# 3_-_STM32F103_Debugger.net
KiCad netlist of a schematic drawn in Altium Designer
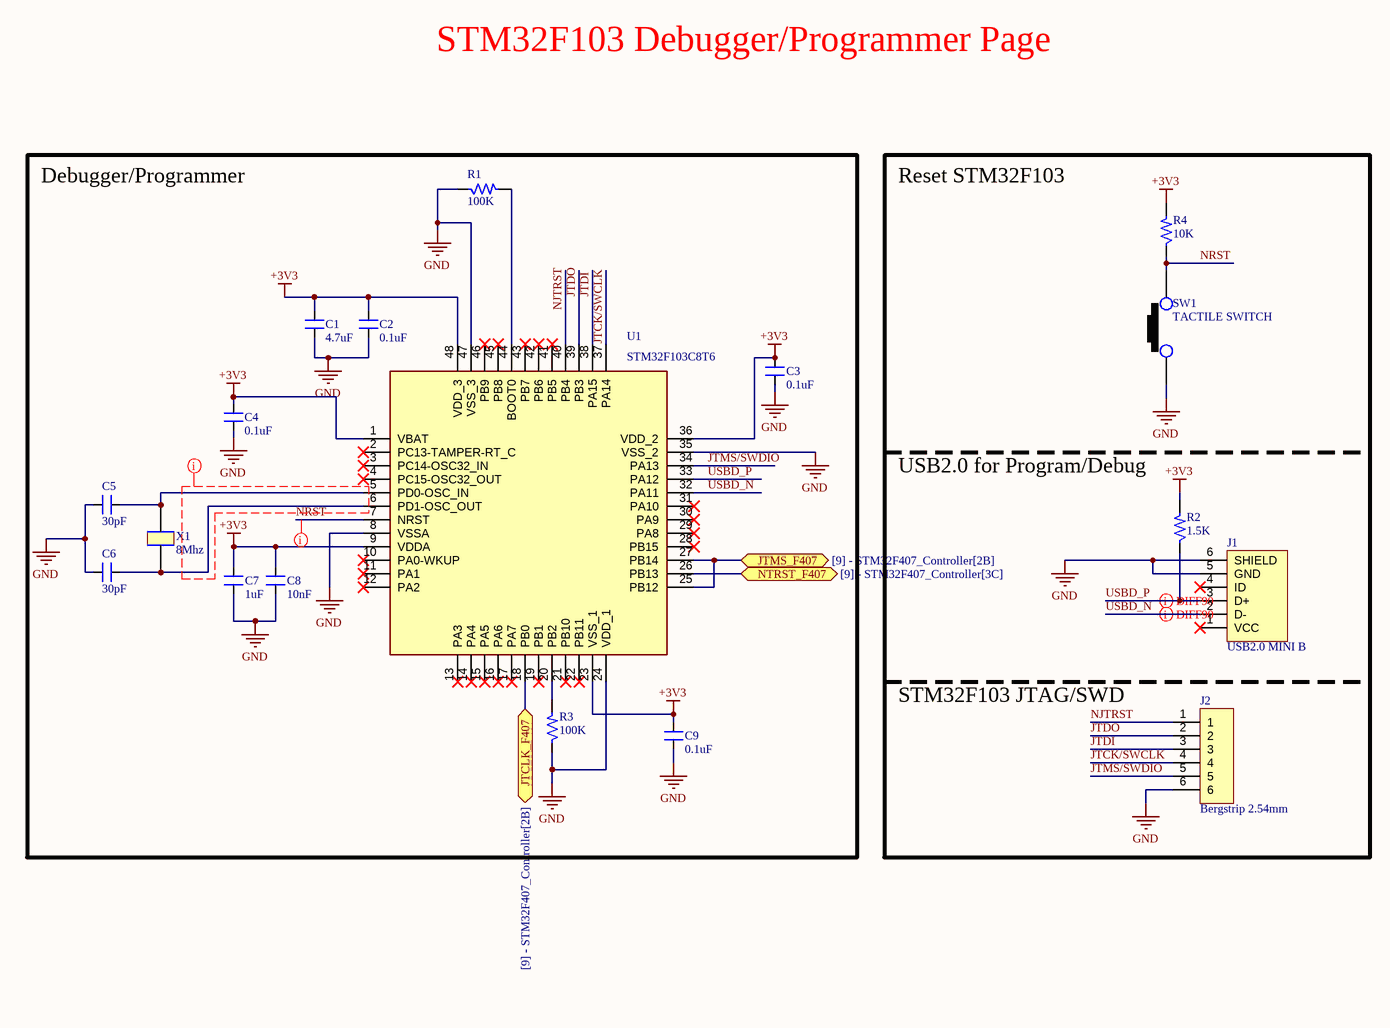
[diagram p0: [3] - STM32F103_Debugger.SchDoc]

(export (version "E")
  (design (tool "Eeschema 10.0.6"))
  (components
    (comp (ref "C1")
      (value "4.7uF")
      (footprint "CAP_0805")
      (description "4.7µF ±10% 50V Ceramic Capacitor X5R 0805 (2012 Metric)")
      (fields
        (field (name "MANUFACTURER") "Yageo")
        (field (name "MANUFACTURER PART NUMBER") "GRM21BR61H475KE51L")
      )
      (libsource (lib "ESTEEMPCBLIB") (part "CAP_4.7uF-50V-10%-0805"))
    )
    (comp (ref "C2")
      (value "0.1uF")
      (footprint "CAP_0805")
      (description "0.1µF ±5% 50V Ceramic Capacitor X7R 0805 (2012 Metric)")
      (fields
        (field (name "MANUFACTURER") "AVX Corporation")
        (field (name "MANUFACTURER PART NUMBER") "08055C104JAT4A")
      )
      (libsource (lib "ESTEEMPCBLIB") (part "CAP_0.1uF-50V-5%-0805"))
    )
    (comp (ref "C3")
      (value "0.1uF")
      (footprint "CAP_0805")
      (description "0.1µF ±5% 50V Ceramic Capacitor X7R 0805 (2012 Metric)")
      (fields
        (field (name "MANUFACTURER") "AVX Corporation")
        (field (name "MANUFACTURER PART NUMBER") "08055C104JAT4A")
      )
      (libsource (lib "ESTEEMPCBLIB") (part "CAP_0.1uF-50V-5%-0805"))
    )
    (comp (ref "C4")
      (value "0.1uF")
      (footprint "CAP_0805")
      (description "0.1µF ±5% 50V Ceramic Capacitor X7R 0805 (2012 Metric)")
      (fields
        (field (name "MANUFACTURER") "AVX Corporation")
        (field (name "MANUFACTURER PART NUMBER") "08055C104JAT4A")
      )
      (libsource (lib "ESTEEMPCBLIB") (part "CAP_0.1uF-50V-5%-0805"))
    )
    (comp (ref "C5")
      (value "30pF")
      (footprint "CAP_0805")
      (description "±10% 50V Ceramic Capacitor C0G, NP0 0805 (2012 Metric)")
      (fields
        (field (name "MANUFACTURER PART NUMBER") "C0805C300K5GAC7800")
        (field (name "MANUFACTURER") "KEMET")
      )
      (libsource (lib "ESTEEMPCBLIB") (part "CAP_30pF-50V-10%-0805"))
    )
    (comp (ref "C6")
      (value "30pF")
      (footprint "CAP_0805")
      (description "±10% 50V Ceramic Capacitor C0G, NP0 0805 (2012 Metric)")
      (fields
        (field (name "MANUFACTURER PART NUMBER") "C0805C300K5GAC7800")
        (field (name "MANUFACTURER") "KEMET")
      )
      (libsource (lib "ESTEEMPCBLIB") (part "CAP_30pF-50V-10%-0805"))
    )
    (comp (ref "C7")
      (value "1uF")
      (footprint "CAP_0805")
      (description "1µF ±5% 50V Ceramic Capacitor X7R 0805 (2012 Metric)")
      (fields
        (field (name "MANUFACTURER") "Samsung")
        (field (name "MANUFACTURER PART NUMBER") "CC0805JKX7R9BB105")
      )
      (libsource (lib "ESTEEMPCBLIB") (part "CAP_1uF-50V-5%-0805"))
    )
    (comp (ref "C8")
      (value "10nF")
      (footprint "CAP_0805")
      (description "10000pF ±10% 50V Ceramic Capacitor X7R 0805 (2012 Metric)")
      (fields
        (field (name "MANUFACTURER") "Samsung")
        (field (name "MANUFACTURER PART NUMBER") "C0805C103K5RECAUTO")
      )
      (libsource (lib "ESTEEMPCBLIB") (part "CAP_10nF-50V-10%-0805"))
    )
    (comp (ref "C9")
      (value "0.1uF")
      (footprint "CAP_0805")
      (description "0.1µF ±5% 50V Ceramic Capacitor X7R 0805 (2012 Metric)")
      (fields
        (field (name "MANUFACTURER") "AVX Corporation")
        (field (name "MANUFACTURER PART NUMBER") "08055C104JAT4A")
      )
      (libsource (lib "ESTEEMPCBLIB") (part "CAP_0.1uF-50V-5%-0805"))
    )
    (comp (ref "J1")
      (value "USB2.0 MINI B")
      (footprint "CON_690-005-299-043")
      (description "USB - mini B USB 2.0 Receptacle Connector 5 Position Surface Mount, Right Angle")
      (fields
        (field (name "MANUFACTURER") "EDAC")
        (field (name "MANUFACTURER PART NUMBER") "690-005-299-043")
      )
      (libsource (lib "ESTEEMPCBLIB") (part "CON_USB2.0-MINIB-SMD"))
    )
    (comp (ref "J2")
      (value "Bergstrip 2.54mm")
      (footprint "CON6_100_59D78_TH_ST")
      (description "6 Pins, 1 Row 2.54mm Pitch, Straight bergstrip, Female")
      (fields (field (name "MANUFACTURER") "Molex") (field (name "MANUFACTURER PART NUMBER") "22-10-2061"))
      (libsource (lib "ESTEEMPCBLIB") (part "CON-BS-SKT_6X1-100-ST-TH"))
    )
    (comp (ref "R1")
      (value "100K")
      (footprint "RES_0805")
      (description "100 kOhms ±1% 0.125W, 1/8W Chip Resistor 0805 (2012 Metric) Automotive AEC-Q200 Thick Film")
      (fields (field (name "MANUFACTURER") "Walsin") (field (name "MANUFACTURER PART NUMBER") "WR08X1003FTL"))
      (libsource (lib "ESTEEMPCBLIB") (part "RES_100K-0.125W-1%-0805"))
    )
    (comp (ref "R2")
      (value "1.5K")
      (footprint "RES_0805")
      (description "1.5 kOhms ±1% 0.125W, 1/8W Chip Resistor 0805 (2012 Metric) Thick Film")
      (fields
        (field (name "MANUFACTURER") "TE Connectivity Passive Product")
        (field (name "MANUFACTURER PART NUMBER") "CRG0805F1K5")
      )
      (libsource (lib "ESTEEMPCBLIB") (part "RES_1.5K-0.125W-1%-0805"))
    )
    (comp (ref "R3")
      (value "100K")
      (footprint "RES_0805")
      (description "100 kOhms ±1% 0.125W, 1/8W Chip Resistor 0805 (2012 Metric) Automotive AEC-Q200 Thick Film")
      (fields (field (name "MANUFACTURER") "Walsin") (field (name "MANUFACTURER PART NUMBER") "WR08X1003FTL"))
      (libsource (lib "ESTEEMPCBLIB") (part "RES_100K-0.125W-1%-0805"))
    )
    (comp (ref "R4")
      (value "10K")
      (footprint "RES_0805")
      (description "10 kOhms ±1% 0.125W, 1/8W Chip Resistor 0805 (2012 Metric) Automotive AEC-Q200 Thick Film")
      (fields (field (name "MANUFACTURER") "CTS") (field (name "MANUFACTURER PART NUMBER") "WR08X1002FTL"))
      (libsource (lib "ESTEEMPCBLIB") (part "RES_10K-0.125W-1%-0805"))
    )
    (comp (ref "SW1")
      (value "TACTILE SWITCH")
      (footprint "SW_342_SMD")
      (description "Tactile Switch SPST-NO Top Actuated Surface Mount")
      (fields
        (field (name "MANUFACTURER") "ITT C&K")
        (field (name "MANUFACTURER PART NUMBER") "RS-282G05A3-SMRT")
      )
      (libsource (lib "ESTEEMPCBLIB") (part "SW1_RS-282G05A3-SMRT-SMD"))
    )
    (comp (ref "U1")
      (value "STM32F103C8T6")
      (footprint "LQFP-48_19.6_393_58X11_SMD")
      (description "ARM® Cortex®-M3 STM32F1 Microcontroller IC 32-Bit 72MHz 64KB (64K x 8) FLASH 48-LQFP (7x7)")
      (fields (field (name "MANUFACTURER") "STMicroelectronics"))
      (libsource (lib "ESTEEMPCBLIB") (part "IC_STM32F103C8T6"))
    )
    (comp (ref "X1")
      (value "8Mhz")
      (footprint "XTAL_314_240X47_SMD")
      (description "8MHz ±30ppm Crystal 32pF 60 Ohms HC-49/US")
      (fields
        (field (name "MANUFACTURER") "Fox Electronics")
        (field (name "MANUFACTURER PART NUMBER") "ECS-80-32-5PX-TR")
      )
      (libsource (lib "ESTEEMPCBLIB") (part "XTAL_8MHZ-ECS-80-32-5PX-SMD"))
    )
  )
  (nets
    (net (code "1") (name "+3V3") (class "Default")
      (node (ref "C1") (pin "2") (pinfunction "2_2") (pintype "passive"))
      (node (ref "C2") (pin "2") (pinfunction "2_2") (pintype "passive"))
      (node (ref "C3") (pin "2") (pinfunction "2_2") (pintype "passive"))
      (node (ref "C4") (pin "2") (pinfunction "2_2") (pintype "passive"))
      (node (ref "C7") (pin "2") (pinfunction "2_2") (pintype "passive"))
      (node (ref "C8") (pin "2") (pinfunction "2_2") (pintype "passive"))
      (node (ref "C9") (pin "2") (pinfunction "2_2") (pintype "passive"))
      (node (ref "R2") (pin "2") (pinfunction "2_2") (pintype "passive"))
      (node (ref "R4") (pin "2") (pinfunction "2_2") (pintype "passive"))
      (node (ref "U1") (pin "1") (pinfunction "VBAT_1") (pintype "passive"))
      (node (ref "U1") (pin "23") (pinfunction "VSS_1_23") (pintype "passive"))
      (node (ref "U1") (pin "36") (pinfunction "VDD_2_36") (pintype "passive"))
      (node (ref "U1") (pin "48") (pinfunction "VDD_3_48") (pintype "passive"))
      (node (ref "U1") (pin "9") (pinfunction "VDDA_9") (pintype "passive"))
    )
    (net (code "2") (name "/JTCK{slash}SWCLK") (class "Default")
      (node (ref "J2") (pin "4") (pinfunction "4_4") (pintype "passive"))
      (node (ref "U1") (pin "37") (pinfunction "PA14_37") (pintype "passive"))
    )
    (net (code "3") (name "/JTCLK_F407") (class "Default")
      (node (ref "U1") (pin "18") (pinfunction "PB0_18") (pintype "passive"))
    )
    (net (code "4") (name "/JTDI") (class "Default")
      (node (ref "J2") (pin "3") (pinfunction "3_3") (pintype "passive"))
      (node (ref "U1") (pin "38") (pinfunction "PA15_38") (pintype "passive"))
    )
    (net (code "5") (name "/JTDO") (class "Default")
      (node (ref "J2") (pin "2") (pinfunction "2_2") (pintype "passive"))
      (node (ref "U1") (pin "39") (pinfunction "PB3_39") (pintype "passive"))
    )
    (net (code "6") (name "/JTMS_F407") (class "Default")
      (node (ref "U1") (pin "25") (pinfunction "PB12_25") (pintype "passive"))
      (node (ref "U1") (pin "27") (pinfunction "PB14_27") (pintype "passive"))
    )
    (net (code "7") (name "/JTMS{slash}SWDIO") (class "Default")
      (node (ref "J2") (pin "5") (pinfunction "5_5") (pintype "passive"))
      (node (ref "U1") (pin "34") (pinfunction "PA13_34") (pintype "passive"))
    )
    (net (code "8") (name "/NJTRST") (class "Default")
      (node (ref "J2") (pin "1") (pinfunction "1_1") (pintype "passive"))
      (node (ref "U1") (pin "40") (pinfunction "PB4_40") (pintype "passive"))
    )
    (net (code "9") (name "/NRST") (class "Default")
      (node (ref "R4") (pin "1") (pinfunction "1_1") (pintype "passive"))
      (node (ref "SW1") (pin "2") (pinfunction "2_2") (pintype "passive"))
      (node (ref "U1") (pin "7") (pinfunction "NRST_7") (pintype "passive"))
    )
    (net (code "10") (name "/NTRST_F407") (class "Default")
      (node (ref "U1") (pin "26") (pinfunction "PB13_26") (pintype "passive"))
    )
    (net (code "11") (name "/USBD_N") (class "Default")
      (node (ref "J1") (pin "2") (pinfunction "D-_2") (pintype "passive"))
      (node (ref "U1") (pin "32") (pinfunction "PA11_32") (pintype "passive"))
    )
    (net (code "12") (name "/USBD_P") (class "Default")
      (node (ref "J1") (pin "3") (pinfunction "D+_3") (pintype "passive"))
      (node (ref "R2") (pin "1") (pinfunction "1_1") (pintype "passive"))
      (node (ref "U1") (pin "33") (pinfunction "PA12_33") (pintype "passive"))
    )
    (net (code "13") (name "GND") (class "Default")
      (node (ref "C1") (pin "1") (pinfunction "1_1") (pintype "passive"))
      (node (ref "C2") (pin "1") (pinfunction "1_1") (pintype "passive"))
      (node (ref "C3") (pin "1") (pinfunction "1_1") (pintype "passive"))
      (node (ref "C4") (pin "1") (pinfunction "1_1") (pintype "passive"))
      (node (ref "C5") (pin "1") (pinfunction "1_1") (pintype "passive"))
      (node (ref "C6") (pin "1") (pinfunction "1_1") (pintype "passive"))
      (node (ref "C7") (pin "1") (pinfunction "1_1") (pintype "passive"))
      (node (ref "C8") (pin "1") (pinfunction "1_1") (pintype "passive"))
      (node (ref "C9") (pin "1") (pinfunction "1_1") (pintype "passive"))
      (node (ref "J1") (pin "5") (pinfunction "GND_5") (pintype "passive"))
      (node (ref "J1") (pin "6") (pinfunction "SHIELD_6") (pintype "passive"))
      (node (ref "J2") (pin "6") (pinfunction "6_6") (pintype "passive"))
      (node (ref "R1") (pin "1") (pinfunction "1_1") (pintype "passive"))
      (node (ref "R3") (pin "1") (pinfunction "1_1") (pintype "passive"))
      (node (ref "SW1") (pin "1") (pinfunction "1_1") (pintype "passive"))
      (node (ref "U1") (pin "24") (pinfunction "VDD_1_24") (pintype "passive"))
      (node (ref "U1") (pin "35") (pinfunction "VSS_2_35") (pintype "passive"))
      (node (ref "U1") (pin "47") (pinfunction "VSS_3_47") (pintype "passive"))
      (node (ref "U1") (pin "8") (pinfunction "VSSA_8") (pintype "passive"))
    )
    (net (code "14") (name "Net-(U1-BOOT0)") (class "Default")
      (node (ref "R1") (pin "2") (pinfunction "2_2") (pintype "passive"))
      (node (ref "U1") (pin "44") (pinfunction "BOOT0_44") (pintype "passive"))
    )
    (net (code "15") (name "Net-(U1-PB2)") (class "Default")
      (node (ref "R3") (pin "2") (pinfunction "2_2") (pintype "passive"))
      (node (ref "U1") (pin "20") (pinfunction "PB2_20") (pintype "passive"))
    )
    (net (code "16") (name "Net-(U1-PD0-OSC_IN)") (class "Default")
      (node (ref "C5") (pin "2") (pinfunction "2_2") (pintype "passive"))
      (node (ref "U1") (pin "5") (pinfunction "PD0-OSC_IN_5") (pintype "passive"))
      (node (ref "X1") (pin "2") (pinfunction "2_2") (pintype "passive"))
    )
    (net (code "17") (name "Net-(U1-PD1-OSC_OUT)") (class "Default")
      (node (ref "C6") (pin "2") (pinfunction "2_2") (pintype "passive"))
      (node (ref "U1") (pin "6") (pinfunction "PD1-OSC_OUT_6") (pintype "passive"))
      (node (ref "X1") (pin "1") (pinfunction "1_1") (pintype "passive"))
    )
    (net (code "18") (name "unconnected-(J1-ID-Pad4)") (class "Default")
      (node (ref "J1") (pin "4") (pinfunction "ID_4") (pintype "passive+no_connect"))
    )
    (net (code "19") (name "unconnected-(J1-VCC-Pad1)") (class "Default")
      (node (ref "J1") (pin "1") (pinfunction "VCC_1") (pintype "passive+no_connect"))
    )
    (net (code "20") (name "unconnected-(U1-PA0-WKUP-Pad10)") (class "Default")
      (node (ref "U1") (pin "10") (pinfunction "PA0-WKUP_10") (pintype "passive+no_connect"))
    )
    (net (code "21") (name "unconnected-(U1-PA1-Pad11)") (class "Default")
      (node (ref "U1") (pin "11") (pinfunction "PA1_11") (pintype "passive+no_connect"))
    )
    (net (code "22") (name "unconnected-(U1-PA2-Pad12)") (class "Default")
      (node (ref "U1") (pin "12") (pinfunction "PA2_12") (pintype "passive+no_connect"))
    )
    (net (code "23") (name "unconnected-(U1-PA3-Pad13)") (class "Default")
      (node (ref "U1") (pin "13") (pinfunction "PA3_13") (pintype "passive+no_connect"))
    )
    (net (code "24") (name "unconnected-(U1-PA4-Pad14)") (class "Default")
      (node (ref "U1") (pin "14") (pinfunction "PA4_14") (pintype "passive+no_connect"))
    )
    (net (code "25") (name "unconnected-(U1-PA5-Pad15)") (class "Default")
      (node (ref "U1") (pin "15") (pinfunction "PA5_15") (pintype "passive+no_connect"))
    )
    (net (code "26") (name "unconnected-(U1-PA6-Pad16)") (class "Default")
      (node (ref "U1") (pin "16") (pinfunction "PA6_16") (pintype "passive+no_connect"))
    )
    (net (code "27") (name "unconnected-(U1-PA7-Pad17)") (class "Default")
      (node (ref "U1") (pin "17") (pinfunction "PA7_17") (pintype "passive+no_connect"))
    )
    (net (code "28") (name "unconnected-(U1-PA8-Pad29)") (class "Default")
      (node (ref "U1") (pin "29") (pinfunction "PA8_29") (pintype "passive+no_connect"))
    )
    (net (code "29") (name "unconnected-(U1-PA9-Pad30)") (class "Default")
      (node (ref "U1") (pin "30") (pinfunction "PA9_30") (pintype "passive+no_connect"))
    )
    (net (code "30") (name "unconnected-(U1-PA10-Pad31)") (class "Default")
      (node (ref "U1") (pin "31") (pinfunction "PA10_31") (pintype "passive+no_connect"))
    )
    (net (code "31") (name "unconnected-(U1-PB1-Pad19)") (class "Default")
      (node (ref "U1") (pin "19") (pinfunction "PB1_19") (pintype "passive+no_connect"))
    )
    (net (code "32") (name "unconnected-(U1-PB5-Pad41)") (class "Default")
      (node (ref "U1") (pin "41") (pinfunction "PB5_41") (pintype "passive+no_connect"))
    )
    (net (code "33") (name "unconnected-(U1-PB6-Pad42)") (class "Default")
      (node (ref "U1") (pin "42") (pinfunction "PB6_42") (pintype "passive+no_connect"))
    )
    (net (code "34") (name "unconnected-(U1-PB7-Pad43)") (class "Default")
      (node (ref "U1") (pin "43") (pinfunction "PB7_43") (pintype "passive+no_connect"))
    )
    (net (code "35") (name "unconnected-(U1-PB8-Pad45)") (class "Default")
      (node (ref "U1") (pin "45") (pinfunction "PB8_45") (pintype "passive+no_connect"))
    )
    (net (code "36") (name "unconnected-(U1-PB9-Pad46)") (class "Default")
      (node (ref "U1") (pin "46") (pinfunction "PB9_46") (pintype "passive+no_connect"))
    )
    (net (code "37") (name "unconnected-(U1-PB10-Pad21)") (class "Default")
      (node (ref "U1") (pin "21") (pinfunction "PB10_21") (pintype "passive+no_connect"))
    )
    (net (code "38") (name "unconnected-(U1-PB11-Pad22)") (class "Default")
      (node (ref "U1") (pin "22") (pinfunction "PB11_22") (pintype "passive+no_connect"))
    )
    (net (code "39") (name "unconnected-(U1-PB15-Pad28)") (class "Default")
      (node (ref "U1") (pin "28") (pinfunction "PB15_28") (pintype "passive+no_connect"))
    )
    (net (code "40") (name "unconnected-(U1-PC13-TAMPER-RT_C-Pad2)") (class "Default")
      (node (ref "U1") (pin "2") (pinfunction "PC13-TAMPER-RT_C_2") (pintype "passive+no_connect"))
    )
    (net (code "41") (name "unconnected-(U1-PC14-OSC32_IN-Pad3)") (class "Default")
      (node (ref "U1") (pin "3") (pinfunction "PC14-OSC32_IN_3") (pintype "passive+no_connect"))
    )
    (net (code "42") (name "unconnected-(U1-PC15-OSC32_OUT-Pad4)") (class "Default")
      (node (ref "U1") (pin "4") (pinfunction "PC15-OSC32_OUT_4") (pintype "passive+no_connect"))
    )
  )
)
